# AD620.net
KiCad netlist of a schematic drawn in EAGLE
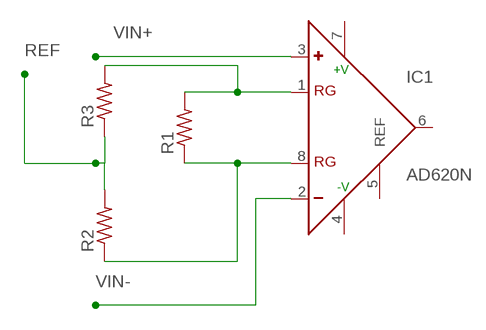
[diagram p0: schematic, sheet 1]

(export (version "E")
  (design (tool "Eeschema 10.0.6"))
  (components
    (comp (ref "IC1")
      (value "AD620N")
      (footprint "eagle-import:DIL08")
      (fields (field (name "MF") "ALTERA CORPORATION") (field (name "MPN") "AD620AN"))
      (libsource (lib "eagle-import") (part "AD620N"))
    )
    (comp (ref "R1")
      (value "R-US_0204/5")
      (footprint "eagle-import:0204_5")
      (libsource (lib "eagle-import") (part "R-US_0204/5"))
    )
    (comp (ref "R2")
      (value "R-US_0204/5")
      (footprint "eagle-import:0204_5")
      (libsource (lib "eagle-import") (part "R-US_0204/5"))
    )
    (comp (ref "R3")
      (value "R-US_0204/5")
      (footprint "eagle-import:0204_5")
      (libsource (lib "eagle-import") (part "R-US_0204/5"))
    )
  )
  (nets
    (net (code "1") (name "/+V") (class "Default")
      (node (ref "IC1") (pin "7") (pinfunction "+V_7") (pintype "power_in"))
    )
    (net (code "2") (name "/-V") (class "Default")
      (node (ref "IC1") (pin "4") (pinfunction "-V_4") (pintype "power_in"))
    )
    (net (code "3") (name "/REF") (class "Default")
      (node (ref "R2") (pin "2") (pinfunction "2_2") (pintype "passive"))
      (node (ref "R3") (pin "1") (pinfunction "1_1") (pintype "passive"))
    )
    (net (code "4") (name "/VIN+") (class "Default")
      (node (ref "IC1") (pin "3") (pinfunction "+_3") (pintype "input"))
    )
    (net (code "5") (name "/VIN-") (class "Default")
      (node (ref "IC1") (pin "2") (pinfunction "-_2") (pintype "input"))
    )
    (net (code "6") (name "Net-(IC1-RG-Pad1)") (class "Default")
      (node (ref "IC1") (pin "1") (pinfunction "RG_1") (pintype "passive"))
      (node (ref "R1") (pin "2") (pinfunction "2_2") (pintype "passive"))
      (node (ref "R3") (pin "2") (pinfunction "2_2") (pintype "passive"))
    )
    (net (code "7") (name "Net-(IC1-RG-Pad8)") (class "Default")
      (node (ref "IC1") (pin "8") (pinfunction "RG_8") (pintype "passive"))
      (node (ref "R1") (pin "1") (pinfunction "1_1") (pintype "passive"))
      (node (ref "R2") (pin "1") (pinfunction "1_1") (pintype "passive"))
    )
    (net (code "8") (name "unconnected-(IC1-OUT-Pad6)") (class "Default")
      (node (ref "IC1") (pin "6") (pinfunction "OUT_6") (pintype "output"))
    )
    (net (code "9") (name "unconnected-(IC1-REF-Pad5)") (class "Default")
      (node (ref "IC1") (pin "5") (pinfunction "REF_5") (pintype "passive"))
    )
  )
)
